# 1-Schematic_5G8038.net
KiCad netlist of a schematic drawn in EasyEDA
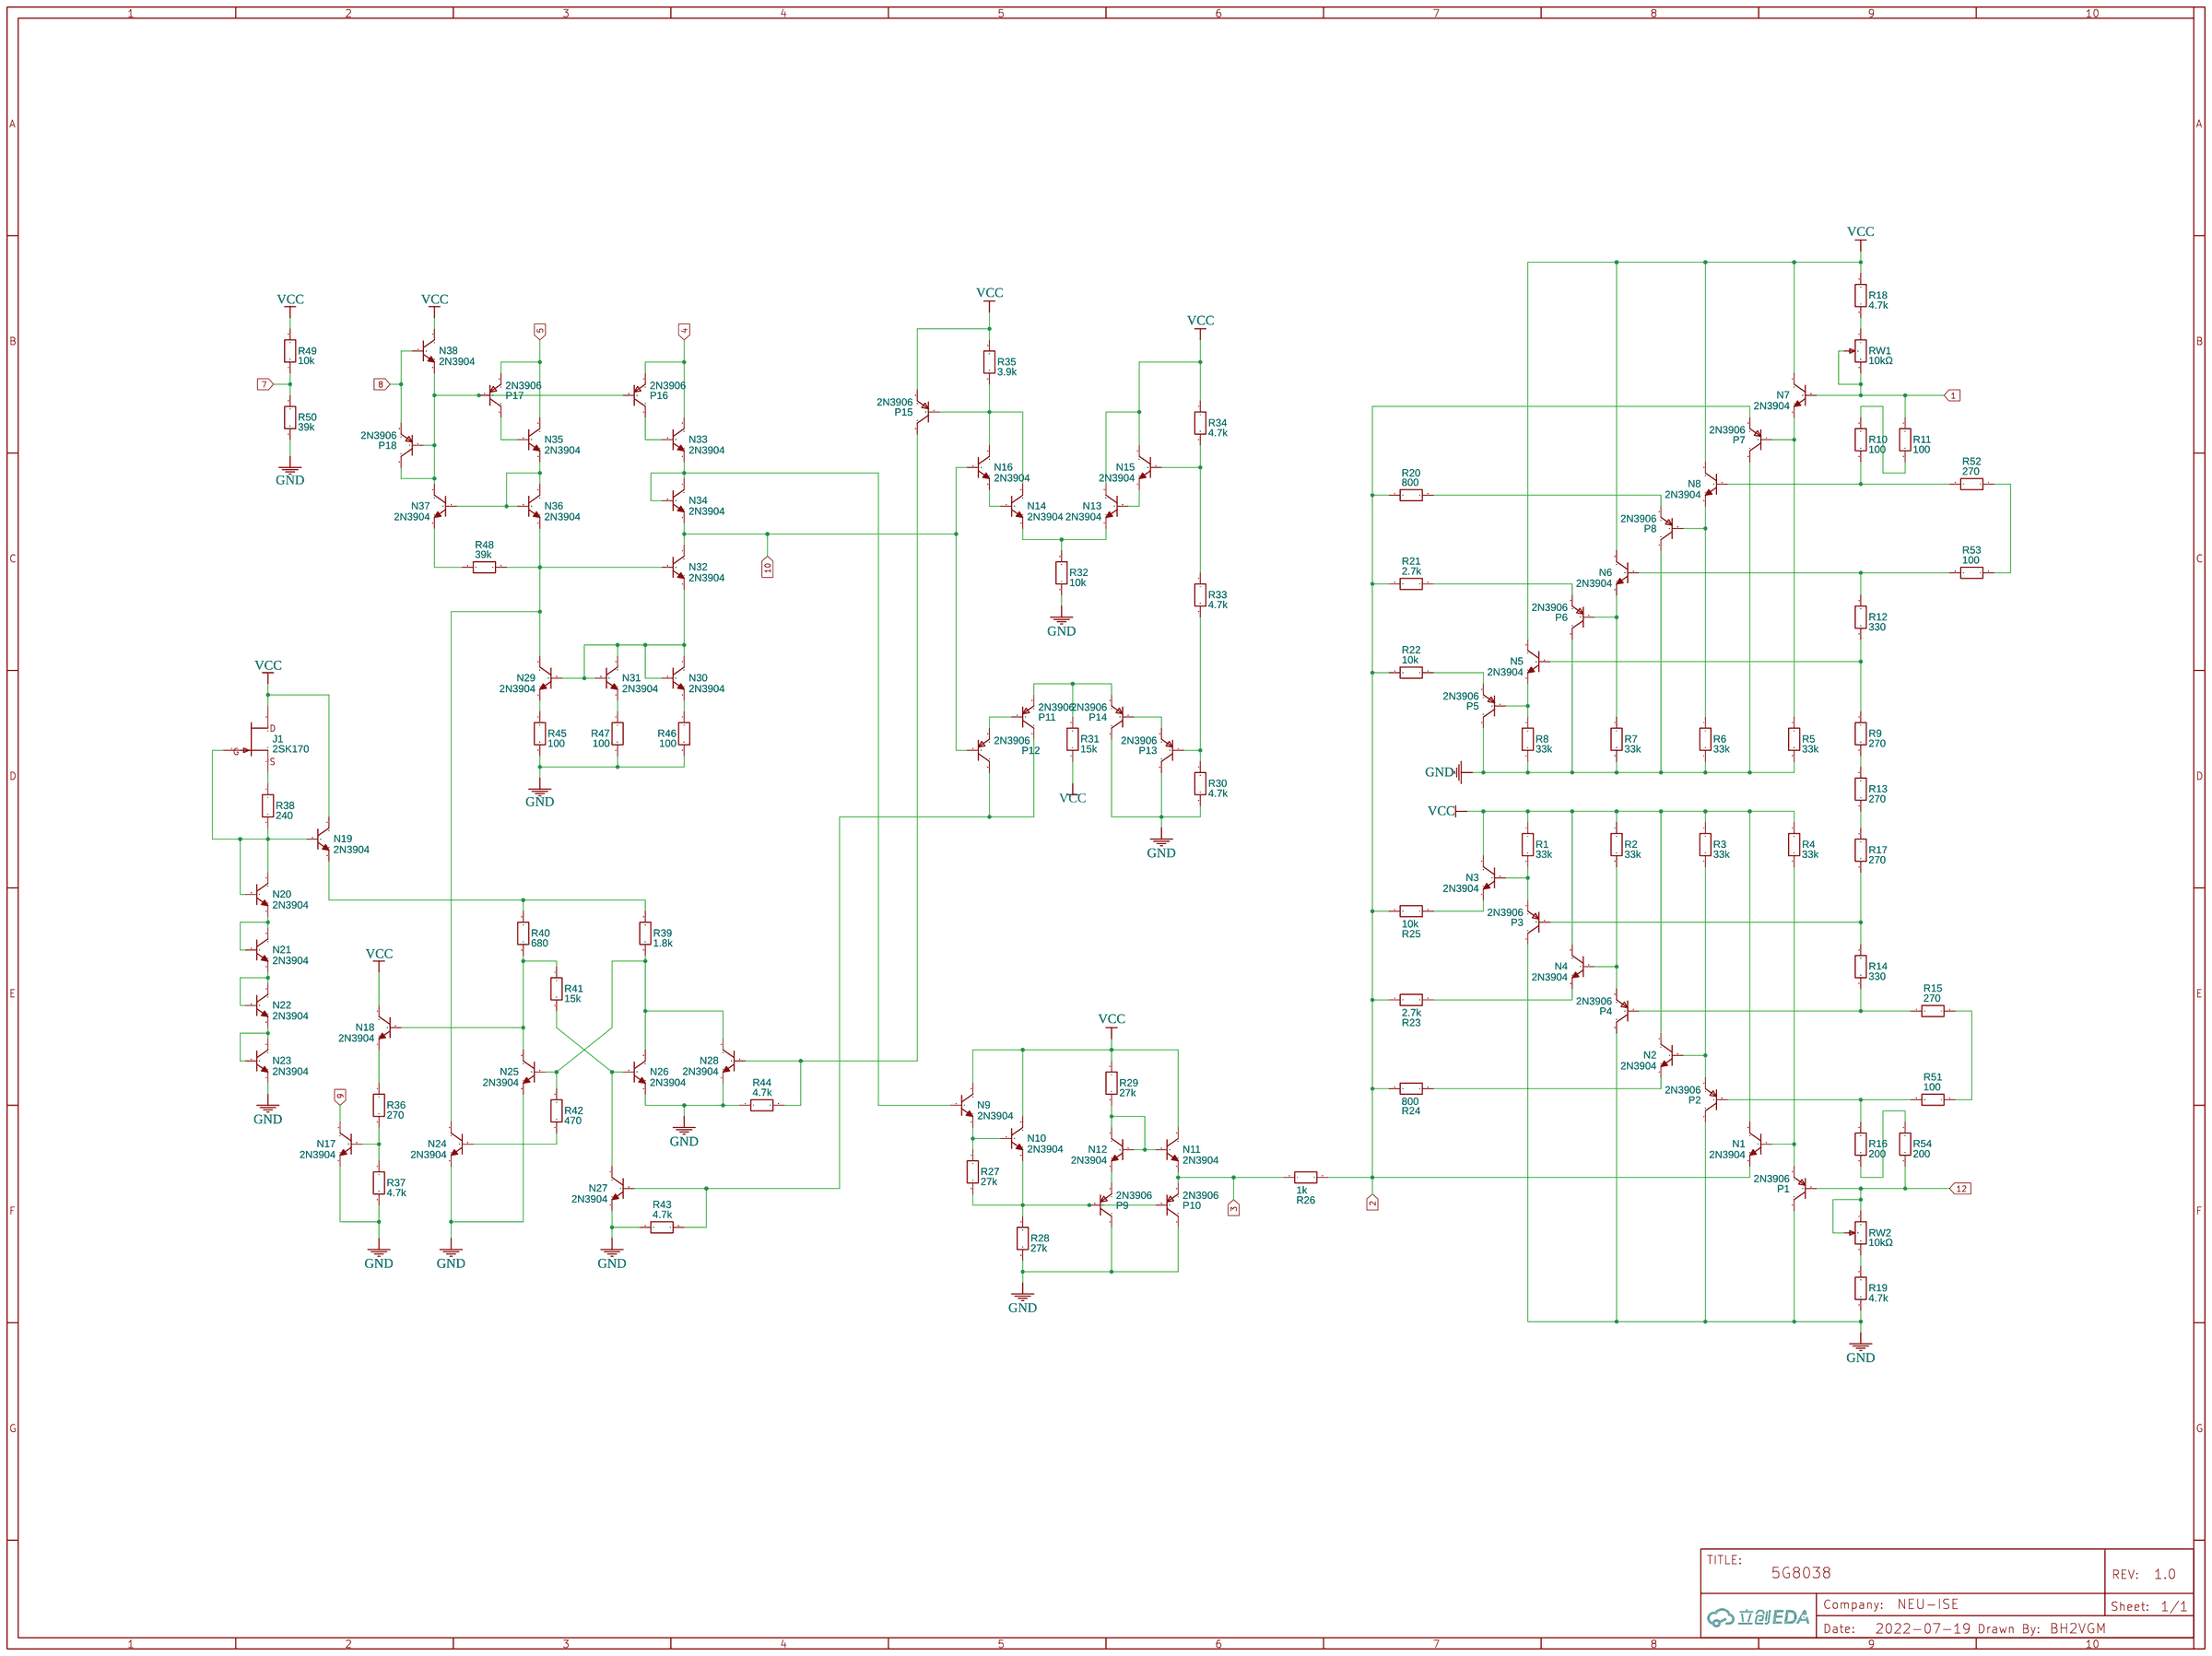
[diagram p0: schematic sheet]

(export (version "E")
  (design (tool "Eeschema 10.0.6"))
  (components
    (comp (ref "J1") (value "2SK170") (libsource (lib "") (part "2SK170")))
    (comp (ref "N1")
      (value "2N3904")
      (fields (field (name "BOM_Supplier Part") "C118538"))
      (libsource (lib "") (part "2N3904"))
    )
    (comp (ref "N2")
      (value "2N3904")
      (fields (field (name "BOM_Supplier Part") "C118538"))
      (libsource (lib "") (part "2N3904"))
    )
    (comp (ref "N3")
      (value "2N3904")
      (fields (field (name "BOM_Supplier Part") "C118538"))
      (libsource (lib "") (part "2N3904"))
    )
    (comp (ref "N4")
      (value "2N3904")
      (fields (field (name "BOM_Supplier Part") "C118538"))
      (libsource (lib "") (part "2N3904"))
    )
    (comp (ref "N5")
      (value "2N3904")
      (fields (field (name "BOM_Supplier Part") "C118538"))
      (libsource (lib "") (part "2N3904"))
    )
    (comp (ref "N6")
      (value "2N3904")
      (fields (field (name "BOM_Supplier Part") "C118538"))
      (libsource (lib "") (part "2N3904"))
    )
    (comp (ref "N7")
      (value "2N3904")
      (fields (field (name "BOM_Supplier Part") "C118538"))
      (libsource (lib "") (part "2N3904"))
    )
    (comp (ref "N8")
      (value "2N3904")
      (fields (field (name "BOM_Supplier Part") "C118538"))
      (libsource (lib "") (part "2N3904"))
    )
    (comp (ref "N9")
      (value "2N3904")
      (fields (field (name "BOM_Supplier Part") "C118538"))
      (libsource (lib "") (part "2N3904_1"))
    )
    (comp (ref "N10")
      (value "2N3904")
      (fields (field (name "BOM_Supplier Part") "C118538"))
      (libsource (lib "") (part "2N3904_1"))
    )
    (comp (ref "N11")
      (value "2N3904")
      (fields (field (name "BOM_Supplier Part") "C118538"))
      (libsource (lib "") (part "2N3904_1"))
    )
    (comp (ref "N12")
      (value "2N3904")
      (fields (field (name "BOM_Supplier Part") "C118538"))
      (libsource (lib "") (part "2N3904"))
    )
    (comp (ref "N13")
      (value "2N3904")
      (fields (field (name "BOM_Supplier Part") "C118538"))
      (libsource (lib "") (part "2N3904"))
    )
    (comp (ref "N14")
      (value "2N3904")
      (fields (field (name "BOM_Supplier Part") "C118538"))
      (libsource (lib "") (part "2N3904_1"))
    )
    (comp (ref "N15")
      (value "2N3904")
      (fields (field (name "BOM_Supplier Part") "C118538"))
      (libsource (lib "") (part "2N3904"))
    )
    (comp (ref "N16")
      (value "2N3904")
      (fields (field (name "BOM_Supplier Part") "C118538"))
      (libsource (lib "") (part "2N3904_1"))
    )
    (comp (ref "N17")
      (value "2N3904")
      (fields (field (name "BOM_Supplier Part") "C118538"))
      (libsource (lib "") (part "2N3904"))
    )
    (comp (ref "N18")
      (value "2N3904")
      (fields (field (name "BOM_Supplier Part") "C118538"))
      (libsource (lib "") (part "2N3904"))
    )
    (comp (ref "N19")
      (value "2N3904")
      (fields (field (name "BOM_Supplier Part") "C118538"))
      (libsource (lib "") (part "2N3904_1"))
    )
    (comp (ref "N20")
      (value "2N3904")
      (fields (field (name "BOM_Supplier Part") "C118538"))
      (libsource (lib "") (part "2N3904_1"))
    )
    (comp (ref "N21")
      (value "2N3904")
      (fields (field (name "BOM_Supplier Part") "C118538"))
      (libsource (lib "") (part "2N3904_1"))
    )
    (comp (ref "N22")
      (value "2N3904")
      (fields (field (name "BOM_Supplier Part") "C118538"))
      (libsource (lib "") (part "2N3904_1"))
    )
    (comp (ref "N23")
      (value "2N3904")
      (fields (field (name "BOM_Supplier Part") "C118538"))
      (libsource (lib "") (part "2N3904_1"))
    )
    (comp (ref "N24")
      (value "2N3904")
      (fields (field (name "BOM_Supplier Part") "C118538"))
      (libsource (lib "") (part "2N3904"))
    )
    (comp (ref "N25")
      (value "2N3904")
      (fields (field (name "BOM_Supplier Part") "C118538"))
      (libsource (lib "") (part "2N3904"))
    )
    (comp (ref "N26")
      (value "2N3904")
      (fields (field (name "BOM_Supplier Part") "C118538"))
      (libsource (lib "") (part "2N3904_1"))
    )
    (comp (ref "N27")
      (value "2N3904")
      (fields (field (name "BOM_Supplier Part") "C118538"))
      (libsource (lib "") (part "2N3904"))
    )
    (comp (ref "N28")
      (value "2N3904")
      (fields (field (name "BOM_Supplier Part") "C118538"))
      (libsource (lib "") (part "2N3904"))
    )
    (comp (ref "N29")
      (value "2N3904")
      (fields (field (name "BOM_Supplier Part") "C118538"))
      (libsource (lib "") (part "2N3904"))
    )
    (comp (ref "N30")
      (value "2N3904")
      (fields (field (name "BOM_Supplier Part") "C118538"))
      (libsource (lib "") (part "2N3904_1"))
    )
    (comp (ref "N31")
      (value "2N3904")
      (fields (field (name "BOM_Supplier Part") "C118538"))
      (libsource (lib "") (part "2N3904_1"))
    )
    (comp (ref "N32")
      (value "2N3904")
      (fields (field (name "BOM_Supplier Part") "C118538"))
      (libsource (lib "") (part "2N3904_1"))
    )
    (comp (ref "N33")
      (value "2N3904")
      (fields (field (name "BOM_Supplier Part") "C118538"))
      (libsource (lib "") (part "2N3904_1"))
    )
    (comp (ref "N34")
      (value "2N3904")
      (fields (field (name "BOM_Supplier Part") "C118538"))
      (libsource (lib "") (part "2N3904_1"))
    )
    (comp (ref "N35")
      (value "2N3904")
      (fields (field (name "BOM_Supplier Part") "C118538"))
      (libsource (lib "") (part "2N3904_1"))
    )
    (comp (ref "N36")
      (value "2N3904")
      (fields (field (name "BOM_Supplier Part") "C118538"))
      (libsource (lib "") (part "2N3904_1"))
    )
    (comp (ref "N37")
      (value "2N3904")
      (fields (field (name "BOM_Supplier Part") "C118538"))
      (libsource (lib "") (part "2N3904"))
    )
    (comp (ref "N38")
      (value "2N3904")
      (fields (field (name "BOM_Supplier Part") "C118538"))
      (libsource (lib "") (part "2N3904_1"))
    )
    (comp (ref "P1")
      (value "2N3906")
      (fields (field (name "BOM_Supplier Part") "C9809"))
      (libsource (lib "") (part "2N3906_1"))
    )
    (comp (ref "P2")
      (value "2N3906")
      (fields (field (name "BOM_Supplier Part") "C9809"))
      (libsource (lib "") (part "2N3906_1"))
    )
    (comp (ref "P3")
      (value "2N3906")
      (fields (field (name "BOM_Supplier Part") "C9809"))
      (libsource (lib "") (part "2N3906_1"))
    )
    (comp (ref "P4")
      (value "2N3906")
      (fields (field (name "BOM_Supplier Part") "C9809"))
      (libsource (lib "") (part "2N3906_1"))
    )
    (comp (ref "P5")
      (value "2N3906")
      (fields (field (name "BOM_Supplier Part") "C9809"))
      (libsource (lib "") (part "2N3906_1"))
    )
    (comp (ref "P6")
      (value "2N3906")
      (fields (field (name "BOM_Supplier Part") "C9809"))
      (libsource (lib "") (part "2N3906_1"))
    )
    (comp (ref "P7")
      (value "2N3906")
      (fields (field (name "BOM_Supplier Part") "C9809"))
      (libsource (lib "") (part "2N3906_1"))
    )
    (comp (ref "P8")
      (value "2N3906")
      (fields (field (name "BOM_Supplier Part") "C9809"))
      (libsource (lib "") (part "2N3906_1"))
    )
    (comp (ref "P9")
      (value "2N3906")
      (fields (field (name "BOM_Supplier Part") "C9809"))
      (libsource (lib "") (part "2N3906"))
    )
    (comp (ref "P10")
      (value "2N3906")
      (fields (field (name "BOM_Supplier Part") "C9809"))
      (libsource (lib "") (part "2N3906"))
    )
    (comp (ref "P11")
      (value "2N3906")
      (fields (field (name "BOM_Supplier Part") "C9809"))
      (libsource (lib "") (part "2N3906"))
    )
    (comp (ref "P12")
      (value "2N3906")
      (fields (field (name "BOM_Supplier Part") "C9809"))
      (libsource (lib "") (part "2N3906"))
    )
    (comp (ref "P13")
      (value "2N3906")
      (fields (field (name "BOM_Supplier Part") "C9809"))
      (libsource (lib "") (part "2N3906_1"))
    )
    (comp (ref "P14")
      (value "2N3906")
      (fields (field (name "BOM_Supplier Part") "C9809"))
      (libsource (lib "") (part "2N3906_1"))
    )
    (comp (ref "P15")
      (value "2N3906")
      (fields (field (name "BOM_Supplier Part") "C9809"))
      (libsource (lib "") (part "2N3906_1"))
    )
    (comp (ref "P16")
      (value "2N3906")
      (fields (field (name "BOM_Supplier Part") "C9809"))
      (libsource (lib "") (part "2N3906"))
    )
    (comp (ref "P17")
      (value "2N3906")
      (fields (field (name "BOM_Supplier Part") "C9809"))
      (libsource (lib "") (part "2N3906"))
    )
    (comp (ref "P18")
      (value "2N3906")
      (fields (field (name "BOM_Supplier Part") "C9809"))
      (libsource (lib "") (part "2N3906_1"))
    )
    (comp (ref "R1") (value "33k") (libsource (lib "") (part "1/4W电阻")))
    (comp (ref "R2") (value "33k") (libsource (lib "") (part "1/4W电阻")))
    (comp (ref "R3") (value "33k") (libsource (lib "") (part "1/4W电阻")))
    (comp (ref "R4") (value "33k") (libsource (lib "") (part "1/4W电阻")))
    (comp (ref "R5") (value "33k") (libsource (lib "") (part "1/4W电阻")))
    (comp (ref "R6") (value "33k") (libsource (lib "") (part "1/4W电阻")))
    (comp (ref "R7") (value "33k") (libsource (lib "") (part "1/4W电阻")))
    (comp (ref "R8") (value "33k") (libsource (lib "") (part "1/4W电阻")))
    (comp (ref "R9") (value "270") (libsource (lib "") (part "1/4W电阻")))
    (comp (ref "R10") (value "100") (libsource (lib "") (part "1/4W电阻")))
    (comp (ref "R11") (value "100") (libsource (lib "") (part "1/4W电阻")))
    (comp (ref "R12") (value "330") (libsource (lib "") (part "1/4W电阻")))
    (comp (ref "R13") (value "270") (libsource (lib "") (part "1/4W电阻")))
    (comp (ref "R14") (value "330") (libsource (lib "") (part "1/4W电阻_2")))
    (comp (ref "R15") (value "270") (libsource (lib "") (part "1/4W电阻_3")))
    (comp (ref "R16") (value "200") (libsource (lib "") (part "1/4W电阻_2")))
    (comp (ref "R17") (value "270") (libsource (lib "") (part "1/4W电阻")))
    (comp (ref "R18") (value "4.7k") (libsource (lib "") (part "1/4W电阻")))
    (comp (ref "R19") (value "4.7k") (libsource (lib "") (part "1/4W电阻_2")))
    (comp (ref "R20") (value "800") (libsource (lib "") (part "1/4W电阻_1")))
    (comp (ref "R21") (value "2.7k") (libsource (lib "") (part "1/4W电阻_1")))
    (comp (ref "R22") (value "10k") (libsource (lib "") (part "1/4W电阻_1")))
    (comp (ref "R23") (value "2.7k") (libsource (lib "") (part "1/4W电阻_1")))
    (comp (ref "R24") (value "800") (libsource (lib "") (part "1/4W电阻_1")))
    (comp (ref "R25") (value "10k") (libsource (lib "") (part "1/4W电阻_1")))
    (comp (ref "R26") (value "1k") (libsource (lib "") (part "1/4W电阻_1")))
    (comp (ref "R27") (value "27k") (libsource (lib "") (part "1/4W电阻")))
    (comp (ref "R28") (value "27k") (libsource (lib "") (part "1/4W电阻")))
    (comp (ref "R29") (value "27k") (libsource (lib "") (part "1/4W电阻")))
    (comp (ref "R30") (value "4.7k") (libsource (lib "") (part "1/4W电阻")))
    (comp (ref "R31") (value "15k") (libsource (lib "") (part "1/4W电阻_2")))
    (comp (ref "R32") (value "10k") (libsource (lib "") (part "1/4W电阻_2")))
    (comp (ref "R33") (value "4.7k") (libsource (lib "") (part "1/4W电阻")))
    (comp (ref "R34") (value "4.7k") (libsource (lib "") (part "1/4W电阻")))
    (comp (ref "R35") (value "3.9k") (libsource (lib "") (part "1/4W电阻")))
    (comp (ref "R36") (value "270") (libsource (lib "") (part "1/4W电阻")))
    (comp (ref "R37") (value "4.7k") (libsource (lib "") (part "1/4W电阻")))
    (comp (ref "R38") (value "240") (libsource (lib "") (part "1/4W电阻")))
    (comp (ref "R39") (value "1.8k") (libsource (lib "") (part "1/4W电阻")))
    (comp (ref "R40") (value "680") (libsource (lib "") (part "1/4W电阻")))
    (comp (ref "R41") (value "15k") (libsource (lib "") (part "1/4W电阻")))
    (comp (ref "R42") (value "470") (libsource (lib "") (part "1/4W电阻")))
    (comp (ref "R43") (value "4.7k") (libsource (lib "") (part "1/4W电阻_1")))
    (comp (ref "R44") (value "4.7k") (libsource (lib "") (part "1/4W电阻_1")))
    (comp (ref "R45") (value "100") (libsource (lib "") (part "1/4W电阻")))
    (comp (ref "R46") (value "100") (libsource (lib "") (part "1/4W电阻")))
    (comp (ref "R47") (value "100") (libsource (lib "") (part "1/4W电阻")))
    (comp (ref "R48") (value "39k") (libsource (lib "") (part "1/4W电阻_1")))
    (comp (ref "R49") (value "10k") (libsource (lib "") (part "1/4W电阻_2")))
    (comp (ref "R50") (value "39k") (libsource (lib "") (part "1/4W电阻_2")))
    (comp (ref "R51") (value "100") (libsource (lib "") (part "1/4W电阻_3")))
    (comp (ref "R52") (value "270") (libsource (lib "") (part "1/4W电阻_3")))
    (comp (ref "R53") (value "100") (libsource (lib "") (part "1/4W电阻_3")))
    (comp (ref "R54") (value "200") (libsource (lib "") (part "1/4W电阻_2")))
    (comp (ref "RW1")
      (value "10kΩ")
      (fields
        (field (name "BOM_Manufacturer Part") "3296W-1-103LF")
        (field (name "BOM_Supplier Part") "C34846")
      )
      (libsource (lib "") (part "3296W"))
    )
    (comp (ref "RW2")
      (value "10kΩ")
      (fields
        (field (name "BOM_Manufacturer Part") "3296W-1-103LF")
        (field (name "BOM_Supplier Part") "C34846")
      )
      (libsource (lib "") (part "3296W"))
    )
  )
  (nets
    (net (code "1") (name "1") (class "Default")
      (node (ref "N7") (pin "b") (pinfunction "B_b") (pintype "unspecified"))
      (node (ref "R11") (pin "1") (pinfunction "1_1") (pintype "unspecified"))
      (node (ref "RW1") (pin "2") (pinfunction "2_2") (pintype "input"))
      (node (ref "RW1") (pin "3") (pinfunction "3_3") (pintype "input"))
    )
    (net (code "2") (name "2") (class "Default")
      (node (ref "N1") (pin "e") (pinfunction "E_e") (pintype "unspecified"))
      (node (ref "P7") (pin "e") (pinfunction "E_e") (pintype "unspecified"))
      (node (ref "R20") (pin "1") (pinfunction "1_1") (pintype "unspecified"))
      (node (ref "R21") (pin "1") (pinfunction "1_1") (pintype "unspecified"))
      (node (ref "R22") (pin "1") (pinfunction "1_1") (pintype "unspecified"))
      (node (ref "R23") (pin "1") (pinfunction "1_1") (pintype "unspecified"))
      (node (ref "R24") (pin "1") (pinfunction "1_1") (pintype "unspecified"))
      (node (ref "R25") (pin "1") (pinfunction "1_1") (pintype "unspecified"))
      (node (ref "R26") (pin "2") (pinfunction "2_2") (pintype "unspecified"))
    )
    (net (code "3") (name "3") (class "Default")
      (node (ref "N11") (pin "e") (pinfunction "E_e") (pintype "unspecified"))
      (node (ref "P10") (pin "e") (pinfunction "E_e") (pintype "unspecified"))
      (node (ref "R26") (pin "1") (pinfunction "1_1") (pintype "unspecified"))
    )
    (net (code "4") (name "4") (class "Default")
      (node (ref "N33") (pin "c") (pinfunction "C_c") (pintype "unspecified"))
      (node (ref "P16") (pin "e") (pinfunction "E_e") (pintype "unspecified"))
    )
    (net (code "5") (name "5") (class "Default")
      (node (ref "N35") (pin "c") (pinfunction "C_c") (pintype "unspecified"))
      (node (ref "P17") (pin "e") (pinfunction "E_e") (pintype "unspecified"))
    )
    (net (code "6") (name "7") (class "Default")
      (node (ref "R49") (pin "1") (pinfunction "1_1") (pintype "unspecified"))
      (node (ref "R50") (pin "2") (pinfunction "2_2") (pintype "unspecified"))
    )
    (net (code "7") (name "8") (class "Default")
      (node (ref "N38") (pin "b") (pinfunction "B_b") (pintype "unspecified"))
      (node (ref "P18") (pin "e") (pinfunction "E_e") (pintype "unspecified"))
    )
    (net (code "8") (name "9") (class "Default")
      (node (ref "N17") (pin "c") (pinfunction "C_c") (pintype "unspecified"))
    )
    (net (code "9") (name "10") (class "Default")
      (node (ref "N16") (pin "b") (pinfunction "B_b") (pintype "unspecified"))
      (node (ref "N32") (pin "c") (pinfunction "C_c") (pintype "unspecified"))
      (node (ref "N34") (pin "e") (pinfunction "E_e") (pintype "unspecified"))
      (node (ref "P12") (pin "b") (pinfunction "B_b") (pintype "unspecified"))
    )
    (net (code "10") (name "12") (class "Default")
      (node (ref "P1") (pin "b") (pinfunction "B_b") (pintype "unspecified"))
      (node (ref "R54") (pin "1") (pinfunction "1_1") (pintype "unspecified"))
      (node (ref "RW2") (pin "1") (pinfunction "1_1") (pintype "input"))
      (node (ref "RW2") (pin "2") (pinfunction "2_2") (pintype "input"))
    )
    (net (code "11") (name "GND") (class "Default")
      (node (ref "N17") (pin "e") (pinfunction "E_e") (pintype "unspecified"))
      (node (ref "N23") (pin "e") (pinfunction "E_e") (pintype "unspecified"))
      (node (ref "N24") (pin "e") (pinfunction "E_e") (pintype "unspecified"))
      (node (ref "N25") (pin "e") (pinfunction "E_e") (pintype "unspecified"))
      (node (ref "N26") (pin "e") (pinfunction "E_e") (pintype "unspecified"))
      (node (ref "N27") (pin "e") (pinfunction "E_e") (pintype "unspecified"))
      (node (ref "N28") (pin "e") (pinfunction "E_e") (pintype "unspecified"))
      (node (ref "P1") (pin "c") (pinfunction "C_c") (pintype "unspecified"))
      (node (ref "P10") (pin "c") (pinfunction "C_c") (pintype "unspecified"))
      (node (ref "P13") (pin "c") (pinfunction "C_c") (pintype "unspecified"))
      (node (ref "P14") (pin "c") (pinfunction "C_c") (pintype "unspecified"))
      (node (ref "P2") (pin "c") (pinfunction "C_c") (pintype "unspecified"))
      (node (ref "P3") (pin "c") (pinfunction "C_c") (pintype "unspecified"))
      (node (ref "P4") (pin "c") (pinfunction "C_c") (pintype "unspecified"))
      (node (ref "P5") (pin "c") (pinfunction "C_c") (pintype "unspecified"))
      (node (ref "P6") (pin "c") (pinfunction "C_c") (pintype "unspecified"))
      (node (ref "P7") (pin "c") (pinfunction "C_c") (pintype "unspecified"))
      (node (ref "P8") (pin "c") (pinfunction "C_c") (pintype "unspecified"))
      (node (ref "P9") (pin "c") (pinfunction "C_c") (pintype "unspecified"))
      (node (ref "R19") (pin "1") (pinfunction "1_1") (pintype "unspecified"))
      (node (ref "R28") (pin "2") (pinfunction "2_2") (pintype "unspecified"))
      (node (ref "R30") (pin "2") (pinfunction "2_2") (pintype "unspecified"))
      (node (ref "R32") (pin "1") (pinfunction "1_1") (pintype "unspecified"))
      (node (ref "R37") (pin "2") (pinfunction "2_2") (pintype "unspecified"))
      (node (ref "R43") (pin "1") (pinfunction "1_1") (pintype "unspecified"))
      (node (ref "R44") (pin "1") (pinfunction "1_1") (pintype "unspecified"))
      (node (ref "R45") (pin "2") (pinfunction "2_2") (pintype "unspecified"))
      (node (ref "R46") (pin "2") (pinfunction "2_2") (pintype "unspecified"))
      (node (ref "R47") (pin "2") (pinfunction "2_2") (pintype "unspecified"))
      (node (ref "R5") (pin "2") (pinfunction "2_2") (pintype "unspecified"))
      (node (ref "R50") (pin "1") (pinfunction "1_1") (pintype "unspecified"))
      (node (ref "R6") (pin "2") (pinfunction "2_2") (pintype "unspecified"))
      (node (ref "R7") (pin "2") (pinfunction "2_2") (pintype "unspecified"))
      (node (ref "R8") (pin "2") (pinfunction "2_2") (pintype "unspecified"))
    )
    (net (code "12") (name "Net-(J1-G)") (class "Default")
      (node (ref "J1") (pin "2") (pinfunction "G_2") (pintype "unspecified"))
      (node (ref "N19") (pin "b") (pinfunction "B_b") (pintype "unspecified"))
      (node (ref "N20") (pin "b") (pinfunction "B_b") (pintype "unspecified"))
      (node (ref "N20") (pin "c") (pinfunction "C_c") (pintype "unspecified"))
      (node (ref "R38") (pin "2") (pinfunction "2_2") (pintype "unspecified"))
    )
    (net (code "13") (name "Net-(J1-S)") (class "Default")
      (node (ref "J1") (pin "1") (pinfunction "S_1") (pintype "unspecified"))
      (node (ref "R38") (pin "1") (pinfunction "1_1") (pintype "unspecified"))
    )
    (net (code "14") (name "Net-(N1-B)") (class "Default")
      (node (ref "N1") (pin "b") (pinfunction "B_b") (pintype "unspecified"))
      (node (ref "P1") (pin "e") (pinfunction "E_e") (pintype "unspecified"))
      (node (ref "R4") (pin "2") (pinfunction "2_2") (pintype "unspecified"))
    )
    (net (code "15") (name "Net-(N2-B)") (class "Default")
      (node (ref "N2") (pin "b") (pinfunction "B_b") (pintype "unspecified"))
      (node (ref "P2") (pin "e") (pinfunction "E_e") (pintype "unspecified"))
      (node (ref "R3") (pin "2") (pinfunction "2_2") (pintype "unspecified"))
    )
    (net (code "16") (name "Net-(N2-E)") (class "Default")
      (node (ref "N2") (pin "e") (pinfunction "E_e") (pintype "unspecified"))
      (node (ref "R24") (pin "2") (pinfunction "2_2") (pintype "unspecified"))
    )
    (net (code "17") (name "Net-(N3-B)") (class "Default")
      (node (ref "N3") (pin "b") (pinfunction "B_b") (pintype "unspecified"))
      (node (ref "P3") (pin "e") (pinfunction "E_e") (pintype "unspecified"))
      (node (ref "R1") (pin "2") (pinfunction "2_2") (pintype "unspecified"))
    )
    (net (code "18") (name "Net-(N3-E)") (class "Default")
      (node (ref "N3") (pin "e") (pinfunction "E_e") (pintype "unspecified"))
      (node (ref "R25") (pin "2") (pinfunction "2_2") (pintype "unspecified"))
    )
    (net (code "19") (name "Net-(N4-B)") (class "Default")
      (node (ref "N4") (pin "b") (pinfunction "B_b") (pintype "unspecified"))
      (node (ref "P4") (pin "e") (pinfunction "E_e") (pintype "unspecified"))
      (node (ref "R2") (pin "2") (pinfunction "2_2") (pintype "unspecified"))
    )
    (net (code "20") (name "Net-(N4-E)") (class "Default")
      (node (ref "N4") (pin "e") (pinfunction "E_e") (pintype "unspecified"))
      (node (ref "R23") (pin "2") (pinfunction "2_2") (pintype "unspecified"))
    )
    (net (code "21") (name "Net-(N5-B)") (class "Default")
      (node (ref "N5") (pin "b") (pinfunction "B_b") (pintype "unspecified"))
      (node (ref "R12") (pin "2") (pinfunction "2_2") (pintype "unspecified"))
      (node (ref "R9") (pin "1") (pinfunction "1_1") (pintype "unspecified"))
    )
    (net (code "22") (name "Net-(N5-E)") (class "Default")
      (node (ref "N5") (pin "e") (pinfunction "E_e") (pintype "unspecified"))
      (node (ref "P5") (pin "b") (pinfunction "B_b") (pintype "unspecified"))
      (node (ref "R8") (pin "1") (pinfunction "1_1") (pintype "unspecified"))
    )
    (net (code "23") (name "Net-(N6-B)") (class "Default")
      (node (ref "N6") (pin "b") (pinfunction "B_b") (pintype "unspecified"))
      (node (ref "R12") (pin "1") (pinfunction "1_1") (pintype "unspecified"))
      (node (ref "R53") (pin "2") (pinfunction "2_2") (pintype "unspecified"))
    )
    (net (code "24") (name "Net-(N6-E)") (class "Default")
      (node (ref "N6") (pin "e") (pinfunction "E_e") (pintype "unspecified"))
      (node (ref "P6") (pin "b") (pinfunction "B_b") (pintype "unspecified"))
      (node (ref "R7") (pin "1") (pinfunction "1_1") (pintype "unspecified"))
    )
    (net (code "25") (name "Net-(N7-E)") (class "Default")
      (node (ref "N7") (pin "e") (pinfunction "E_e") (pintype "unspecified"))
      (node (ref "P7") (pin "b") (pinfunction "B_b") (pintype "unspecified"))
      (node (ref "R5") (pin "1") (pinfunction "1_1") (pintype "unspecified"))
    )
    (net (code "26") (name "Net-(N8-B)") (class "Default")
      (node (ref "N8") (pin "b") (pinfunction "B_b") (pintype "unspecified"))
      (node (ref "R10") (pin "2") (pinfunction "2_2") (pintype "unspecified"))
      (node (ref "R52") (pin "2") (pinfunction "2_2") (pintype "unspecified"))
    )
    (net (code "27") (name "Net-(N8-E)") (class "Default")
      (node (ref "N8") (pin "e") (pinfunction "E_e") (pintype "unspecified"))
      (node (ref "P8") (pin "b") (pinfunction "B_b") (pintype "unspecified"))
      (node (ref "R6") (pin "1") (pinfunction "1_1") (pintype "unspecified"))
    )
    (net (code "28") (name "Net-(N10-B)") (class "Default")
      (node (ref "N10") (pin "b") (pinfunction "B_b") (pintype "unspecified"))
      (node (ref "N9") (pin "e") (pinfunction "E_e") (pintype "unspecified"))
      (node (ref "R27") (pin "1") (pinfunction "1_1") (pintype "unspecified"))
    )
    (net (code "29") (name "Net-(N10-E)") (class "Default")
      (node (ref "N10") (pin "e") (pinfunction "E_e") (pintype "unspecified"))
      (node (ref "P10") (pin "b") (pinfunction "B_b") (pintype "unspecified"))
      (node (ref "P9") (pin "b") (pinfunction "B_b") (pintype "unspecified"))
      (node (ref "R27") (pin "2") (pinfunction "2_2") (pintype "unspecified"))
      (node (ref "R28") (pin "1") (pinfunction "1_1") (pintype "unspecified"))
    )
    (net (code "30") (name "Net-(N11-B)") (class "Default")
      (node (ref "N11") (pin "b") (pinfunction "B_b") (pintype "unspecified"))
      (node (ref "N12") (pin "b") (pinfunction "B_b") (pintype "unspecified"))
      (node (ref "N12") (pin "c") (pinfunction "C_c") (pintype "unspecified"))
      (node (ref "R29") (pin "2") (pinfunction "2_2") (pintype "unspecified"))
    )
    (net (code "31") (name "Net-(N12-E)") (class "Default")
      (node (ref "N12") (pin "e") (pinfunction "E_e") (pintype "unspecified"))
      (node (ref "P9") (pin "e") (pinfunction "E_e") (pintype "unspecified"))
    )
    (net (code "32") (name "Net-(N13-B)") (class "Default")
      (node (ref "N13") (pin "b") (pinfunction "B_b") (pintype "unspecified"))
      (node (ref "N15") (pin "e") (pinfunction "E_e") (pintype "unspecified"))
    )
    (net (code "33") (name "Net-(N13-E)") (class "Default")
      (node (ref "N13") (pin "e") (pinfunction "E_e") (pintype "unspecified"))
      (node (ref "N14") (pin "e") (pinfunction "E_e") (pintype "unspecified"))
      (node (ref "R32") (pin "2") (pinfunction "2_2") (pintype "unspecified"))
    )
    (net (code "34") (name "Net-(N14-B)") (class "Default")
      (node (ref "N14") (pin "b") (pinfunction "B_b") (pintype "unspecified"))
      (node (ref "N16") (pin "e") (pinfunction "E_e") (pintype "unspecified"))
    )
    (net (code "35") (name "Net-(N14-C)") (class "Default")
      (node (ref "N14") (pin "c") (pinfunction "C_c") (pintype "unspecified"))
      (node (ref "N16") (pin "c") (pinfunction "C_c") (pintype "unspecified"))
      (node (ref "P15") (pin "b") (pinfunction "B_b") (pintype "unspecified"))
      (node (ref "R35") (pin "2") (pinfunction "2_2") (pintype "unspecified"))
    )
    (net (code "36") (name "Net-(N15-B)") (class "Default")
      (node (ref "N15") (pin "b") (pinfunction "B_b") (pintype "unspecified"))
      (node (ref "R33") (pin "1") (pinfunction "1_1") (pintype "unspecified"))
      (node (ref "R34") (pin "2") (pinfunction "2_2") (pintype "unspecified"))
    )
    (net (code "37") (name "Net-(N17-B)") (class "Default")
      (node (ref "N17") (pin "b") (pinfunction "B_b") (pintype "unspecified"))
      (node (ref "R36") (pin "2") (pinfunction "2_2") (pintype "unspecified"))
      (node (ref "R37") (pin "1") (pinfunction "1_1") (pintype "unspecified"))
    )
    (net (code "38") (name "Net-(N18-B)") (class "Default")
      (node (ref "N18") (pin "b") (pinfunction "B_b") (pintype "unspecified"))
      (node (ref "N25") (pin "c") (pinfunction "C_c") (pintype "unspecified"))
      (node (ref "R40") (pin "2") (pinfunction "2_2") (pintype "unspecified"))
      (node (ref "R41") (pin "1") (pinfunction "1_1") (pintype "unspecified"))
    )
    (net (code "39") (name "Net-(N18-E)") (class "Default")
      (node (ref "N18") (pin "e") (pinfunction "E_e") (pintype "unspecified"))
      (node (ref "R36") (pin "1") (pinfunction "1_1") (pintype "unspecified"))
    )
    (net (code "40") (name "Net-(N19-E)") (class "Default")
      (node (ref "N19") (pin "e") (pinfunction "E_e") (pintype "unspecified"))
      (node (ref "R39") (pin "1") (pinfunction "1_1") (pintype "unspecified"))
      (node (ref "R40") (pin "1") (pinfunction "1_1") (pintype "unspecified"))
    )
    (net (code "41") (name "Net-(N20-E)") (class "Default")
      (node (ref "N20") (pin "e") (pinfunction "E_e") (pintype "unspecified"))
      (node (ref "N21") (pin "b") (pinfunction "B_b") (pintype "unspecified"))
      (node (ref "N21") (pin "c") (pinfunction "C_c") (pintype "unspecified"))
    )
    (net (code "42") (name "Net-(N21-E)") (class "Default")
      (node (ref "N21") (pin "e") (pinfunction "E_e") (pintype "unspecified"))
      (node (ref "N22") (pin "b") (pinfunction "B_b") (pintype "unspecified"))
      (node (ref "N22") (pin "c") (pinfunction "C_c") (pintype "unspecified"))
    )
    (net (code "43") (name "Net-(N22-E)") (class "Default")
      (node (ref "N22") (pin "e") (pinfunction "E_e") (pintype "unspecified"))
      (node (ref "N23") (pin "b") (pinfunction "B_b") (pintype "unspecified"))
      (node (ref "N23") (pin "c") (pinfunction "C_c") (pintype "unspecified"))
    )
    (net (code "44") (name "Net-(N24-B)") (class "Default")
      (node (ref "N24") (pin "b") (pinfunction "B_b") (pintype "unspecified"))
      (node (ref "R42") (pin "2") (pinfunction "2_2") (pintype "unspecified"))
    )
    (net (code "45") (name "Net-(N24-C)") (class "Default")
      (node (ref "N24") (pin "c") (pinfunction "C_c") (pintype "unspecified"))
      (node (ref "N29") (pin "c") (pinfunction "C_c") (pintype "unspecified"))
      (node (ref "N32") (pin "b") (pinfunction "B_b") (pintype "unspecified"))
      (node (ref "N36") (pin "e") (pinfunction "E_e") (pintype "unspecified"))
      (node (ref "R48") (pin "2") (pinfunction "2_2") (pintype "unspecified"))
    )
    (net (code "46") (name "Net-(N25-B)") (class "Default")
      (node (ref "N25") (pin "b") (pinfunction "B_b") (pintype "unspecified"))
      (node (ref "N26") (pin "c") (pinfunction "C_c") (pintype "unspecified"))
      (node (ref "N28") (pin "c") (pinfunction "C_c") (pintype "unspecified"))
      (node (ref "R39") (pin "2") (pinfunction "2_2") (pintype "unspecified"))
      (node (ref "R42") (pin "1") (pinfunction "1_1") (pintype "unspecified"))
    )
    (net (code "47") (name "Net-(N26-B)") (class "Default")
      (node (ref "N26") (pin "b") (pinfunction "B_b") (pintype "unspecified"))
      (node (ref "N27") (pin "c") (pinfunction "C_c") (pintype "unspecified"))
      (node (ref "R41") (pin "2") (pinfunction "2_2") (pintype "unspecified"))
    )
    (net (code "48") (name "Net-(N27-B)") (class "Default")
      (node (ref "N27") (pin "b") (pinfunction "B_b") (pintype "unspecified"))
      (node (ref "P11") (pin "c") (pinfunction "C_c") (pintype "unspecified"))
      (node (ref "P12") (pin "c") (pinfunction "C_c") (pintype "unspecified"))
      (node (ref "R43") (pin "2") (pinfunction "2_2") (pintype "unspecified"))
    )
    (net (code "49") (name "Net-(N28-B)") (class "Default")
      (node (ref "N28") (pin "b") (pinfunction "B_b") (pintype "unspecified"))
      (node (ref "P15") (pin "c") (pinfunction "C_c") (pintype "unspecified"))
      (node (ref "R44") (pin "2") (pinfunction "2_2") (pintype "unspecified"))
    )
    (net (code "50") (name "Net-(N29-B)") (class "Default")
      (node (ref "N29") (pin "b") (pinfunction "B_b") (pintype "unspecified"))
      (node (ref "N30") (pin "b") (pinfunction "B_b") (pintype "unspecified"))
      (node (ref "N30") (pin "c") (pinfunction "C_c") (pintype "unspecified"))
      (node (ref "N31") (pin "b") (pinfunction "B_b") (pintype "unspecified"))
      (node (ref "N31") (pin "c") (pinfunction "C_c") (pintype "unspecified"))
      (node (ref "N32") (pin "e") (pinfunction "E_e") (pintype "unspecified"))
    )
    (net (code "51") (name "Net-(N29-E)") (class "Default")
      (node (ref "N29") (pin "e") (pinfunction "E_e") (pintype "unspecified"))
      (node (ref "R45") (pin "1") (pinfunction "1_1") (pintype "unspecified"))
    )
    (net (code "52") (name "Net-(N30-E)") (class "Default")
      (node (ref "N30") (pin "e") (pinfunction "E_e") (pintype "unspecified"))
      (node (ref "R46") (pin "1") (pinfunction "1_1") (pintype "unspecified"))
    )
    (net (code "53") (name "Net-(N31-E)") (class "Default")
      (node (ref "N31") (pin "e") (pinfunction "E_e") (pintype "unspecified"))
      (node (ref "R47") (pin "1") (pinfunction "1_1") (pintype "unspecified"))
    )
    (net (code "54") (name "Net-(N33-B)") (class "Default")
      (node (ref "N33") (pin "b") (pinfunction "B_b") (pintype "unspecified"))
      (node (ref "P16") (pin "c") (pinfunction "C_c") (pintype "unspecified"))
    )
    (net (code "55") (name "Net-(N33-E)") (class "Default")
      (node (ref "N33") (pin "e") (pinfunction "E_e") (pintype "unspecified"))
      (node (ref "N34") (pin "b") (pinfunction "B_b") (pintype "unspecified"))
      (node (ref "N34") (pin "c") (pinfunction "C_c") (pintype "unspecified"))
      (node (ref "N9") (pin "b") (pinfunction "B_b") (pintype "unspecified"))
    )
    (net (code "56") (name "Net-(N35-B)") (class "Default")
      (node (ref "N35") (pin "b") (pinfunction "B_b") (pintype "unspecified"))
      (node (ref "P17") (pin "c") (pinfunction "C_c") (pintype "unspecified"))
    )
    (net (code "57") (name "Net-(N35-E)") (class "Default")
      (node (ref "N35") (pin "e") (pinfunction "E_e") (pintype "unspecified"))
      (node (ref "N36") (pin "b") (pinfunction "B_b") (pintype "unspecified"))
      (node (ref "N36") (pin "c") (pinfunction "C_c") (pintype "unspecified"))
      (node (ref "N37") (pin "b") (pinfunction "B_b") (pintype "unspecified"))
    )
    (net (code "58") (name "Net-(N37-C)") (class "Default")
      (node (ref "N37") (pin "c") (pinfunction "C_c") (pintype "unspecified"))
      (node (ref "N38") (pin "e") (pinfunction "E_e") (pintype "unspecified"))
      (node (ref "P16") (pin "b") (pinfunction "B_b") (pintype "unspecified"))
      (node (ref "P17") (pin "b") (pinfunction "B_b") (pintype "unspecified"))
      (node (ref "P18") (pin "b") (pinfunction "B_b") (pintype "unspecified"))
      (node (ref "P18") (pin "c") (pinfunction "C_c") (pintype "unspecified"))
    )
    (net (code "59") (name "Net-(N37-E)") (class "Default")
      (node (ref "N37") (pin "e") (pinfunction "E_e") (pintype "unspecified"))
      (node (ref "R48") (pin "1") (pinfunction "1_1") (pintype "unspecified"))
    )
    (net (code "60") (name "Net-(P2-B)") (class "Default")
      (node (ref "P2") (pin "b") (pinfunction "B_b") (pintype "unspecified"))
      (node (ref "R16") (pin "2") (pinfunction "2_2") (pintype "unspecified"))
      (node (ref "R51") (pin "2") (pinfunction "2_2") (pintype "unspecified"))
    )
    (net (code "61") (name "Net-(P3-B)") (class "Default")
      (node (ref "P3") (pin "b") (pinfunction "B_b") (pintype "unspecified"))
      (node (ref "R14") (pin "2") (pinfunction "2_2") (pintype "unspecified"))
      (node (ref "R17") (pin "2") (pinfunction "2_2") (pintype "unspecified"))
    )
    (net (code "62") (name "Net-(P4-B)") (class "Default")
      (node (ref "P4") (pin "b") (pinfunction "B_b") (pintype "unspecified"))
      (node (ref "R14") (pin "1") (pinfunction "1_1") (pintype "unspecified"))
      (node (ref "R15") (pin "2") (pinfunction "2_2") (pintype "unspecified"))
    )
    (net (code "63") (name "Net-(P5-E)") (class "Default")
      (node (ref "P5") (pin "e") (pinfunction "E_e") (pintype "unspecified"))
      (node (ref "R22") (pin "2") (pinfunction "2_2") (pintype "unspecified"))
    )
    (net (code "64") (name "Net-(P6-E)") (class "Default")
      (node (ref "P6") (pin "e") (pinfunction "E_e") (pintype "unspecified"))
      (node (ref "R21") (pin "2") (pinfunction "2_2") (pintype "unspecified"))
    )
    (net (code "65") (name "Net-(P8-E)") (class "Default")
      (node (ref "P8") (pin "e") (pinfunction "E_e") (pintype "unspecified"))
      (node (ref "R20") (pin "2") (pinfunction "2_2") (pintype "unspecified"))
    )
    (net (code "66") (name "Net-(P11-B)") (class "Default")
      (node (ref "P11") (pin "b") (pinfunction "B_b") (pintype "unspecified"))
      (node (ref "P12") (pin "e") (pinfunction "E_e") (pintype "unspecified"))
    )
    (net (code "67") (name "Net-(P11-E)") (class "Default")
      (node (ref "P11") (pin "e") (pinfunction "E_e") (pintype "unspecified"))
      (node (ref "P14") (pin "e") (pinfunction "E_e") (pintype "unspecified"))
      (node (ref "R31") (pin "2") (pinfunction "2_2") (pintype "unspecified"))
    )
    (net (code "68") (name "Net-(P13-B)") (class "Default")
      (node (ref "P13") (pin "b") (pinfunction "B_b") (pintype "unspecified"))
      (node (ref "R30") (pin "1") (pinfunction "1_1") (pintype "unspecified"))
      (node (ref "R33") (pin "2") (pinfunction "2_2") (pintype "unspecified"))
    )
    (net (code "69") (name "Net-(P13-E)") (class "Default")
      (node (ref "P13") (pin "e") (pinfunction "E_e") (pintype "unspecified"))
      (node (ref "P14") (pin "b") (pinfunction "B_b") (pintype "unspecified"))
    )
    (net (code "70") (name "Net-(R10-Pad1)") (class "Default")
      (node (ref "R10") (pin "1") (pinfunction "1_1") (pintype "unspecified"))
      (node (ref "R11") (pin "2") (pinfunction "2_2") (pintype "unspecified"))
    )
    (net (code "71") (name "Net-(R13-Pad1)") (class "Default")
      (node (ref "R13") (pin "1") (pinfunction "1_1") (pintype "unspecified"))
      (node (ref "R9") (pin "2") (pinfunction "2_2") (pintype "unspecified"))
    )
    (net (code "72") (name "Net-(R13-Pad2)") (class "Default")
      (node (ref "R13") (pin "2") (pinfunction "2_2") (pintype "unspecified"))
      (node (ref "R17") (pin "1") (pinfunction "1_1") (pintype "unspecified"))
    )
    (net (code "73") (name "Net-(R15-Pad1)") (class "Default")
      (node (ref "R15") (pin "1") (pinfunction "1_1") (pintype "unspecified"))
      (node (ref "R51") (pin "1") (pinfunction "1_1") (pintype "unspecified"))
    )
    (net (code "74") (name "Net-(R16-Pad1)") (class "Default")
      (node (ref "R16") (pin "1") (pinfunction "1_1") (pintype "unspecified"))
      (node (ref "R54") (pin "2") (pinfunction "2_2") (pintype "unspecified"))
    )
    (net (code "75") (name "Net-(R18-Pad2)") (class "Default")
      (node (ref "R18") (pin "2") (pinfunction "2_2") (pintype "unspecified"))
      (node (ref "RW1") (pin "1") (pinfunction "1_1") (pintype "input"))
    )
    (net (code "76") (name "Net-(R19-Pad2)") (class "Default")
      (node (ref "R19") (pin "2") (pinfunction "2_2") (pintype "unspecified"))
      (node (ref "RW2") (pin "3") (pinfunction "3_3") (pintype "input"))
    )
    (net (code "77") (name "Net-(R52-Pad1)") (class "Default")
      (node (ref "R52") (pin "1") (pinfunction "1_1") (pintype "unspecified"))
      (node (ref "R53") (pin "1") (pinfunction "1_1") (pintype "unspecified"))
    )
    (net (code "78") (name "VCC") (class "Default")
      (node (ref "J1") (pin "3") (pinfunction "D_3") (pintype "unspecified"))
      (node (ref "N1") (pin "c") (pinfunction "C_c") (pintype "unspecified"))
      (node (ref "N10") (pin "c") (pinfunction "C_c") (pintype "unspecified"))
      (node (ref "N11") (pin "c") (pinfunction "C_c") (pintype "unspecified"))
      (node (ref "N13") (pin "c") (pinfunction "C_c") (pintype "unspecified"))
      (node (ref "N15") (pin "c") (pinfunction "C_c") (pintype "unspecified"))
      (node (ref "N18") (pin "c") (pinfunction "C_c") (pintype "unspecified"))
      (node (ref "N19") (pin "c") (pinfunction "C_c") (pintype "unspecified"))
      (node (ref "N2") (pin "c") (pinfunction "C_c") (pintype "unspecified"))
      (node (ref "N3") (pin "c") (pinfunction "C_c") (pintype "unspecified"))
      (node (ref "N38") (pin "c") (pinfunction "C_c") (pintype "unspecified"))
      (node (ref "N4") (pin "c") (pinfunction "C_c") (pintype "unspecified"))
      (node (ref "N5") (pin "c") (pinfunction "C_c") (pintype "unspecified"))
      (node (ref "N6") (pin "c") (pinfunction "C_c") (pintype "unspecified"))
      (node (ref "N7") (pin "c") (pinfunction "C_c") (pintype "unspecified"))
      (node (ref "N8") (pin "c") (pinfunction "C_c") (pintype "unspecified"))
      (node (ref "N9") (pin "c") (pinfunction "C_c") (pintype "unspecified"))
      (node (ref "P15") (pin "e") (pinfunction "E_e") (pintype "unspecified"))
      (node (ref "R1") (pin "1") (pinfunction "1_1") (pintype "unspecified"))
      (node (ref "R18") (pin "1") (pinfunction "1_1") (pintype "unspecified"))
      (node (ref "R2") (pin "1") (pinfunction "1_1") (pintype "unspecified"))
      (node (ref "R29") (pin "1") (pinfunction "1_1") (pintype "unspecified"))
      (node (ref "R3") (pin "1") (pinfunction "1_1") (pintype "unspecified"))
      (node (ref "R31") (pin "1") (pinfunction "1_1") (pintype "unspecified"))
      (node (ref "R34") (pin "1") (pinfunction "1_1") (pintype "unspecified"))
      (node (ref "R35") (pin "1") (pinfunction "1_1") (pintype "unspecified"))
      (node (ref "R4") (pin "1") (pinfunction "1_1") (pintype "unspecified"))
      (node (ref "R49") (pin "2") (pinfunction "2_2") (pintype "unspecified"))
    )
  )
)
